# Li_ion_PRT-BL.net
KiCad netlist of a schematic drawn in Altium Designer
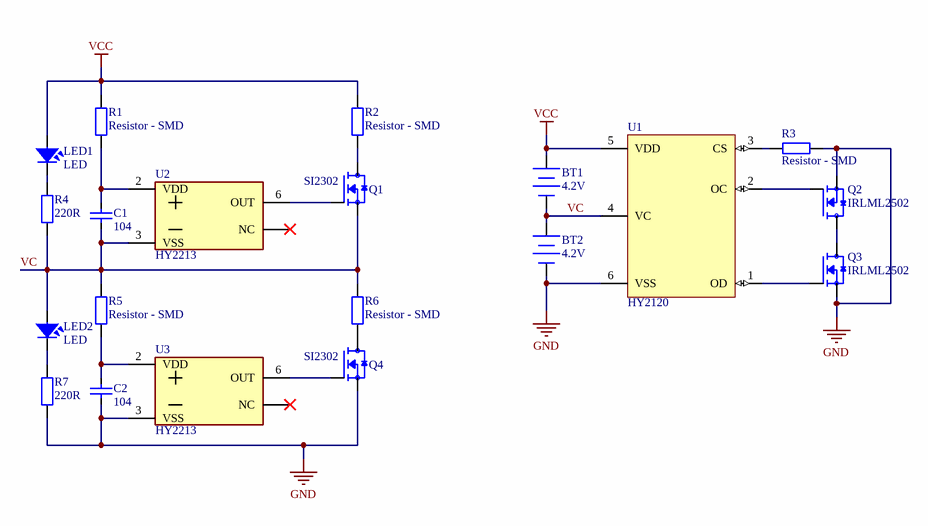
[diagram p0: Li_ion_PRT-BL.SchDoc]

(export (version "E")
  (design (tool "Eeschema 10.0.6"))
  (components
    (comp (ref "BT1")
      (value "4.2V")
      (footprint "My Library:HDR2")
      (description "Multicell Battery")
      (fields (field (name "PUBLISHER") "Altium Limited"))
      (libsource (lib "My Library") (part "Battery3.3V"))
    )
    (comp (ref "BT2")
      (value "4.2V")
      (footprint "My Library:HDR2")
      (description "Multicell Battery")
      (fields (field (name "PUBLISHER") "Altium Limited"))
      (libsource (lib "My Library") (part "Battery3.3V"))
    )
    (comp (ref "C1")
      (value "104")
      (footprint "CAP_0805")
      (description "Capacitor")
      (fields (field (name "PUBLISHER") "Altium Limited"))
      (libsource (lib "My Library") (part "CapSMD"))
    )
    (comp (ref "C2")
      (value "104")
      (footprint "CAP_0805")
      (description "Capacitor")
      (fields (field (name "PUBLISHER") "Altium Limited"))
      (libsource (lib "My Library") (part "CapSMD"))
    )
    (comp (ref "LED1")
      (value "LED")
      (footprint "LED-0805-Blue")
      (description "LED Single colour Green and Red")
      (libsource (lib "My Library") (part "LED"))
    )
    (comp (ref "LED2")
      (value "LED")
      (footprint "LED-0805-Blue")
      (description "LED Single colour Green and Red")
      (libsource (lib "My Library") (part "LED"))
    )
    (comp (ref "Q1")
      (value "SI2302")
      (footprint "My Library:SOT23")
      (libsource (lib "My Library") (part "MOSFET-N"))
    )
    (comp (ref "Q2")
      (value "IRLML2502")
      (footprint "My Library:SOT23")
      (libsource (lib "") (part "MOSFET-N_1"))
    )
    (comp (ref "Q3")
      (value "IRLML2502")
      (footprint "My Library:SOT23")
      (libsource (lib "") (part "MOSFET-N_1"))
    )
    (comp (ref "Q4")
      (value "SI2302")
      (footprint "My Library:SOT23")
      (libsource (lib "My Library") (part "MOSFET-N"))
    )
    (comp (ref "R1")
      (value "Resistor - SMD")
      (footprint "RES-SMD-0805")
      (description "Resistor SMD")
      (fields
        (field (name "MANUFACTURER") "Generic Components")
        (field (name "PUBLISHER") "Altium Hobart Technology Centre")
      )
      (libsource (lib "My Library") (part "Resistor - SMD"))
    )
    (comp (ref "R2")
      (value "Resistor - SMD")
      (footprint "RES-SMD-0805")
      (description "Resistor SMD")
      (fields
        (field (name "MANUFACTURER") "Generic Components")
        (field (name "PUBLISHER") "Altium Hobart Technology Centre")
      )
      (libsource (lib "My Library") (part "Resistor - SMD"))
    )
    (comp (ref "R3")
      (value "Resistor - SMD")
      (footprint "RES-SMD-0805")
      (description "Resistor SMD")
      (fields
        (field (name "MANUFACTURER") "Generic Components")
        (field (name "PUBLISHER") "Altium Hobart Technology Centre")
      )
      (libsource (lib "My Library") (part "Resistor - SMD"))
    )
    (comp (ref "R4")
      (value "220R")
      (footprint "RES-SMD-0805")
      (description "Resistor SMD")
      (fields
        (field (name "MANUFACTURER") "Generic Components")
        (field (name "PUBLISHER") "Altium Hobart Technology Centre")
      )
      (libsource (lib "My Library") (part "Resistor - SMD"))
    )
    (comp (ref "R5")
      (value "Resistor - SMD")
      (footprint "RES-SMD-0805")
      (description "Resistor SMD")
      (fields
        (field (name "MANUFACTURER") "Generic Components")
        (field (name "PUBLISHER") "Altium Hobart Technology Centre")
      )
      (libsource (lib "My Library") (part "Resistor - SMD"))
    )
    (comp (ref "R6")
      (value "Resistor - SMD")
      (footprint "RES-SMD-0805")
      (description "Resistor SMD")
      (fields
        (field (name "MANUFACTURER") "Generic Components")
        (field (name "PUBLISHER") "Altium Hobart Technology Centre")
      )
      (libsource (lib "My Library") (part "Resistor - SMD"))
    )
    (comp (ref "R7")
      (value "220R")
      (footprint "RES-SMD-0805")
      (description "Resistor SMD")
      (fields
        (field (name "MANUFACTURER") "Generic Components")
        (field (name "PUBLISHER") "Altium Hobart Technology Centre")
      )
      (libsource (lib "My Library") (part "Resistor - SMD"))
    )
    (comp (ref "U1")
      (value "HY2120")
      (footprint "My Library:sot23-6")
      (description "2-Cell Lithium-ion/Lithium Polymer Battery Packs Protection ICs")
      (libsource (lib "My Library") (part "HY2120"))
    )
    (comp (ref "U2")
      (value "HY2213")
      (footprint "My Library:SOT23-6")
      (description "1 Cell Li-ion/Polymer Battery Charge Balance IC \r\nMulti-cell Li-ion rechargeable battery packs")
      (libsource (lib "My Library") (part "Battery Charge Balance IC"))
    )
    (comp (ref "U3")
      (value "HY2213")
      (footprint "My Library:SOT23-6")
      (description "1 Cell Li-ion/Polymer Battery Charge Balance IC \r\nMulti-cell Li-ion rechargeable battery packs")
      (libsource (lib "My Library") (part "Battery Charge Balance IC"))
    )
  )
  (nets
    (net (code "1") (name "/VC") (class "Default")
      (node (ref "BT1") (pin "2") (pinfunction "-_2") (pintype "passive"))
      (node (ref "BT2") (pin "1") (pinfunction "+_1") (pintype "passive"))
      (node (ref "C1") (pin "1") (pinfunction "1_1") (pintype "passive"))
      (node (ref "LED2") (pin "1") (pinfunction "1_1") (pintype "passive"))
      (node (ref "Q1") (pin "2") (pinfunction "S_2") (pintype "passive"))
      (node (ref "R4") (pin "2") (pinfunction "2_2") (pintype "passive"))
      (node (ref "R5") (pin "1") (pinfunction "1_1") (pintype "passive"))
      (node (ref "R6") (pin "1") (pinfunction "1_1") (pintype "passive"))
      (node (ref "U1") (pin "4") (pinfunction "VC_4") (pintype "power_in"))
      (node (ref "U2") (pin "3") (pinfunction "VSS_3") (pintype "power_in"))
    )
    (net (code "2") (name "GND") (class "Default")
      (node (ref "BT2") (pin "2") (pinfunction "-_2") (pintype "passive"))
      (node (ref "C2") (pin "1") (pinfunction "1_1") (pintype "passive"))
      (node (ref "Q2") (pin "3") (pinfunction "S_3") (pintype "passive"))
      (node (ref "Q3") (pin "3") (pinfunction "S_3") (pintype "passive"))
      (node (ref "Q4") (pin "2") (pinfunction "S_2") (pintype "passive"))
      (node (ref "R3") (pin "2") (pinfunction "2_2") (pintype "passive"))
      (node (ref "R7") (pin "2") (pinfunction "2_2") (pintype "passive"))
      (node (ref "U1") (pin "6") (pinfunction "VSS_6") (pintype "power_in"))
      (node (ref "U3") (pin "3") (pinfunction "VSS_3") (pintype "power_in"))
    )
    (net (code "3") (name "Net-(LED1-Pad2)") (class "Default")
      (node (ref "LED1") (pin "2") (pinfunction "2_2") (pintype "passive"))
      (node (ref "R4") (pin "1") (pinfunction "1_1") (pintype "passive"))
    )
    (net (code "4") (name "Net-(LED2-Pad2)") (class "Default")
      (node (ref "LED2") (pin "2") (pinfunction "2_2") (pintype "passive"))
      (node (ref "R7") (pin "1") (pinfunction "1_1") (pintype "passive"))
    )
    (net (code "5") (name "Net-(Q1-D)") (class "Default")
      (node (ref "Q1") (pin "3") (pinfunction "D_3") (pintype "passive"))
      (node (ref "R2") (pin "2") (pinfunction "2_2") (pintype "passive"))
    )
    (net (code "6") (name "Net-(Q1-G)") (class "Default")
      (node (ref "Q1") (pin "1") (pinfunction "G_1") (pintype "passive"))
      (node (ref "U2") (pin "6") (pinfunction "OUT_6") (pintype "power_in"))
    )
    (net (code "7") (name "Net-(Q2-D)") (class "Default")
      (node (ref "Q2") (pin "2") (pinfunction "D_2") (pintype "passive"))
      (node (ref "Q3") (pin "2") (pinfunction "D_2") (pintype "passive"))
    )
    (net (code "8") (name "Net-(Q2-G)") (class "Default")
      (node (ref "Q2") (pin "1") (pinfunction "G_1") (pintype "passive"))
      (node (ref "U1") (pin "2") (pinfunction "OC_2") (pintype "bidirectional"))
    )
    (net (code "9") (name "Net-(Q3-G)") (class "Default")
      (node (ref "Q3") (pin "1") (pinfunction "G_1") (pintype "passive"))
      (node (ref "U1") (pin "1") (pinfunction "OD_1") (pintype "bidirectional"))
    )
    (net (code "10") (name "Net-(Q4-D)") (class "Default")
      (node (ref "Q4") (pin "3") (pinfunction "D_3") (pintype "passive"))
      (node (ref "R6") (pin "2") (pinfunction "2_2") (pintype "passive"))
    )
    (net (code "11") (name "Net-(Q4-G)") (class "Default")
      (node (ref "Q4") (pin "1") (pinfunction "G_1") (pintype "passive"))
      (node (ref "U3") (pin "6") (pinfunction "OUT_6") (pintype "power_in"))
    )
    (net (code "12") (name "Net-(U1-CS)") (class "Default")
      (node (ref "R3") (pin "1") (pinfunction "1_1") (pintype "passive"))
      (node (ref "U1") (pin "3") (pinfunction "CS_3") (pintype "bidirectional"))
    )
    (net (code "13") (name "Net-(U2-VDD)") (class "Default")
      (node (ref "C1") (pin "2") (pinfunction "2_2") (pintype "passive"))
      (node (ref "R1") (pin "2") (pinfunction "2_2") (pintype "passive"))
      (node (ref "U2") (pin "2") (pinfunction "VDD_2") (pintype "power_in"))
    )
    (net (code "14") (name "Net-(U3-VDD)") (class "Default")
      (node (ref "C2") (pin "2") (pinfunction "2_2") (pintype "passive"))
      (node (ref "R5") (pin "2") (pinfunction "2_2") (pintype "passive"))
      (node (ref "U3") (pin "2") (pinfunction "VDD_2") (pintype "power_in"))
    )
    (net (code "15") (name "VCC") (class "Default")
      (node (ref "BT1") (pin "1") (pinfunction "+_1") (pintype "passive"))
      (node (ref "LED1") (pin "1") (pinfunction "1_1") (pintype "passive"))
      (node (ref "R1") (pin "1") (pinfunction "1_1") (pintype "passive"))
      (node (ref "R2") (pin "1") (pinfunction "1_1") (pintype "passive"))
      (node (ref "U1") (pin "5") (pinfunction "VDD_5") (pintype "power_in"))
    )
    (net (code "16") (name "unconnected-(U2-NC-Pad1)") (class "Default")
      (node (ref "U2") (pin "1") (pinfunction "NC_1") (pintype "passive+no_connect"))
      (node (ref "U2") (pin "4") (pinfunction "NC_4") (pintype "passive+no_connect"))
      (node (ref "U2") (pin "5") (pinfunction "NC_5") (pintype "passive+no_connect"))
    )
    (net (code "17") (name "unconnected-(U3-NC-Pad1)") (class "Default")
      (node (ref "U3") (pin "1") (pinfunction "NC_1") (pintype "passive+no_connect"))
      (node (ref "U3") (pin "4") (pinfunction "NC_4") (pintype "passive+no_connect"))
      (node (ref "U3") (pin "5") (pinfunction "NC_5") (pintype "passive+no_connect"))
    )
  )
)
